# BleSensor.net
KiCad netlist of a schematic drawn in EAGLE
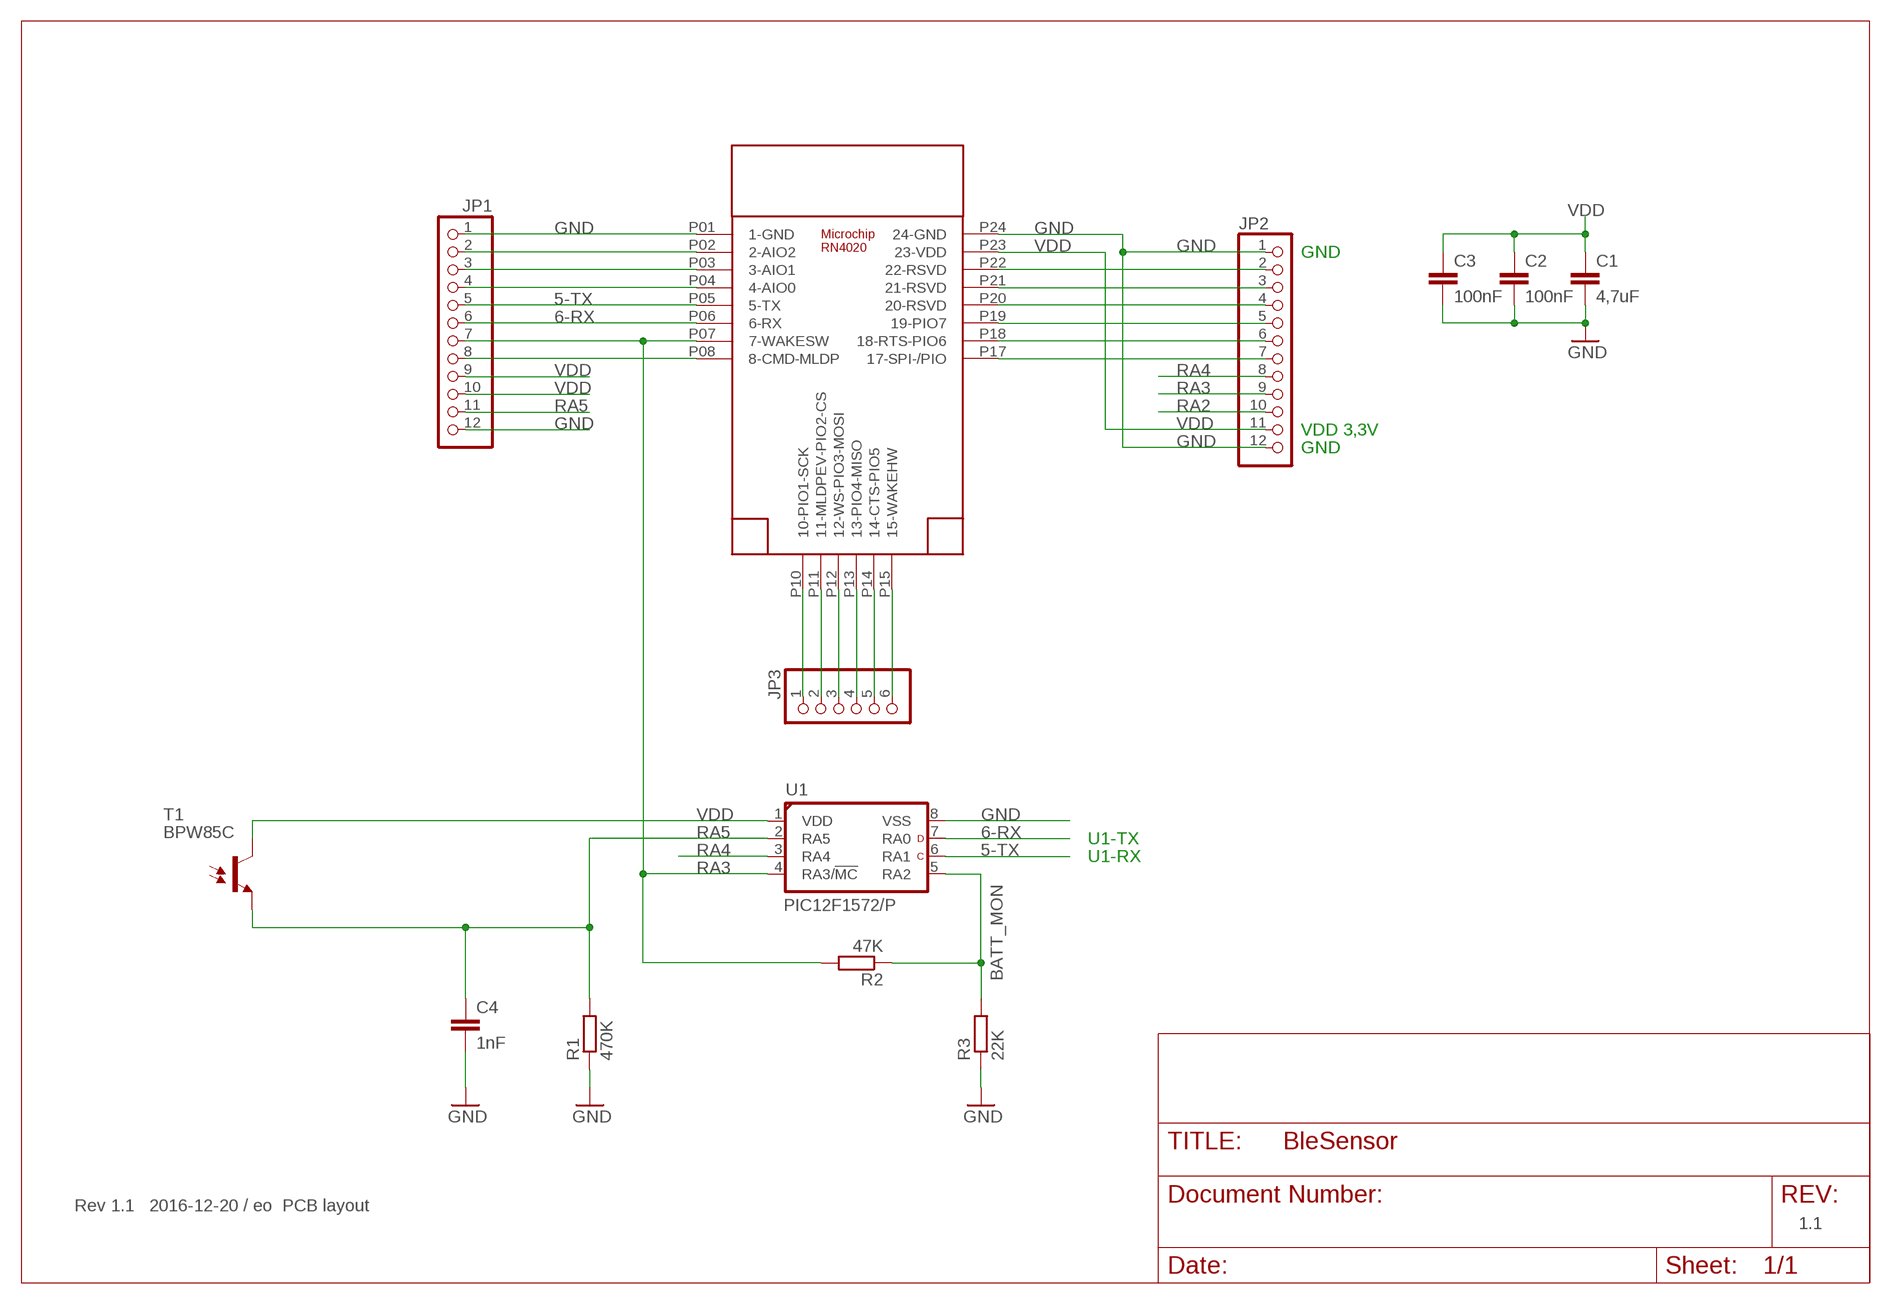
[diagram p0: schematic, sheet 1]

(export (version "E")
  (design (tool "Eeschema 10.0.6"))
  (components
    (comp (ref "C1")
      (value "4,7uF")
      (footprint "eagle-import:C2.5-3")
      (libsource (lib "eagle-import") (part "C2,5-3"))
    )
    (comp (ref "C2")
      (value "100nF")
      (footprint "eagle-import:C1206")
      (libsource (lib "eagle-import") (part "C-EUC1206"))
    )
    (comp (ref "C3")
      (value "100nF")
      (footprint "eagle-import:C1206")
      (libsource (lib "eagle-import") (part "C-EUC1206"))
    )
    (comp (ref "C4")
      (value "1nF")
      (footprint "eagle-import:C1206")
      (libsource (lib "eagle-import") (part "C-EUC1206"))
    )
    (comp (ref "JP1")
      (value "PINHD-1X12")
      (footprint "eagle-import:1X12")
      (libsource (lib "eagle-import") (part "PINHD-1X12"))
    )
    (comp (ref "JP2")
      (value "PINHD-1X12")
      (footprint "eagle-import:1X12")
      (libsource (lib "eagle-import") (part "PINHD-1X12"))
    )
    (comp (ref "JP3")
      (value "PINHD-1X6")
      (footprint "eagle-import:1X06")
      (libsource (lib "eagle-import") (part "PINHD-1X6"))
    )
    (comp (ref "R1")
      (value "470K")
      (footprint "eagle-import:M1206")
      (libsource (lib "eagle-import") (part "R-EU_M1206"))
    )
    (comp (ref "R2")
      (value "47K")
      (footprint "eagle-import:M1206")
      (libsource (lib "eagle-import") (part "R-EU_M1206"))
    )
    (comp (ref "R3")
      (value "22K")
      (footprint "eagle-import:M1206")
      (libsource (lib "eagle-import") (part "R-EU_M1206"))
    )
    (comp (ref "T1")
      (value "BPW85C")
      (footprint "eagle-import:LED3MM")
      (libsource (lib "eagle-import") (part "BPW85C"))
    )
    (comp (ref "U$1")
      (value "RN4020")
      (footprint "eagle-import:RN4020SMD")
      (libsource (lib "eagle-import") (part "RN4020"))
    )
    (comp (ref "U1")
      (value "PIC12F1572/P")
      (footprint "eagle-import:DIL8-P")
      (libsource (lib "eagle-import") (part "PIC12F1572/P"))
    )
  )
  (nets
    (net (code "1") (name "/5-TX") (class "Default")
      (node (ref "JP1") (pin "5") (pinfunction "5_5") (pintype "passive"))
      (node (ref "U$1") (pin "P05") (pinfunction "5-TX_P05") (pintype "bidirectional"))
      (node (ref "U1") (pin "6") (pinfunction "RA1_6") (pintype "bidirectional"))
    )
    (net (code "2") (name "/6-RX") (class "Default")
      (node (ref "JP1") (pin "6") (pinfunction "6_6") (pintype "passive"))
      (node (ref "U$1") (pin "P06") (pinfunction "6-RX_P06") (pintype "bidirectional"))
      (node (ref "U1") (pin "7") (pinfunction "RA0_7") (pintype "bidirectional"))
    )
    (net (code "3") (name "/BATT_MON") (class "Default")
      (node (ref "R2") (pin "1") (pinfunction "1_1") (pintype "passive"))
      (node (ref "R3") (pin "2") (pinfunction "2_2") (pintype "passive"))
      (node (ref "U1") (pin "5") (pinfunction "RA2_5") (pintype "bidirectional"))
    )
    (net (code "4") (name "/RA2") (class "Default")
      (node (ref "JP2") (pin "10") (pinfunction "10_10") (pintype "passive"))
    )
    (net (code "5") (name "/RA3") (class "Default")
      (node (ref "JP1") (pin "7") (pinfunction "7_7") (pintype "passive"))
      (node (ref "JP2") (pin "9") (pinfunction "9_9") (pintype "passive"))
      (node (ref "R2") (pin "2") (pinfunction "2_2") (pintype "passive"))
      (node (ref "U$1") (pin "P07") (pinfunction "7-WAKESW_P07") (pintype "bidirectional"))
      (node (ref "U1") (pin "4") (pinfunction "RA3/~{MC}_4") (pintype "bidirectional"))
    )
    (net (code "6") (name "/RA4") (class "Default")
      (node (ref "JP2") (pin "8") (pinfunction "8_8") (pintype "passive"))
      (node (ref "U1") (pin "3") (pinfunction "RA4_3") (pintype "bidirectional"))
    )
    (net (code "7") (name "/RA5") (class "Default")
      (node (ref "C4") (pin "1") (pinfunction "1_1") (pintype "passive"))
      (node (ref "JP1") (pin "11") (pinfunction "11_11") (pintype "passive"))
      (node (ref "R1") (pin "2") (pinfunction "2_2") (pintype "passive"))
      (node (ref "T1") (pin "A") (pinfunction "E_A") (pintype "passive"))
      (node (ref "U1") (pin "2") (pinfunction "RA5_2") (pintype "bidirectional"))
    )
    (net (code "8") (name "/VDD") (class "Default")
      (node (ref "C1") (pin "1") (pinfunction "1_1") (pintype "passive"))
      (node (ref "C2") (pin "1") (pinfunction "1_1") (pintype "passive"))
      (node (ref "C3") (pin "1") (pinfunction "1_1") (pintype "passive"))
      (node (ref "JP1") (pin "10") (pinfunction "10_10") (pintype "passive"))
      (node (ref "JP1") (pin "9") (pinfunction "9_9") (pintype "passive"))
      (node (ref "JP2") (pin "11") (pinfunction "11_11") (pintype "passive"))
      (node (ref "T1") (pin "K") (pinfunction "C_K") (pintype "passive"))
      (node (ref "U$1") (pin "P23") (pinfunction "23-VDD_P23") (pintype "bidirectional"))
      (node (ref "U1") (pin "1") (pinfunction "VDD_1") (pintype "passive"))
    )
    (net (code "9") (name "GND") (class "Default")
      (node (ref "C1") (pin "2") (pinfunction "2_2") (pintype "passive"))
      (node (ref "C2") (pin "2") (pinfunction "2_2") (pintype "passive"))
      (node (ref "C3") (pin "2") (pinfunction "2_2") (pintype "passive"))
      (node (ref "C4") (pin "2") (pinfunction "2_2") (pintype "passive"))
      (node (ref "JP1") (pin "1") (pinfunction "1_1") (pintype "passive"))
      (node (ref "JP1") (pin "12") (pinfunction "12_12") (pintype "passive"))
      (node (ref "JP2") (pin "1") (pinfunction "1_1") (pintype "passive"))
      (node (ref "JP2") (pin "12") (pinfunction "12_12") (pintype "passive"))
      (node (ref "R1") (pin "1") (pinfunction "1_1") (pintype "passive"))
      (node (ref "R3") (pin "1") (pinfunction "1_1") (pintype "passive"))
      (node (ref "U$1") (pin "P01") (pinfunction "1-GND_P01") (pintype "bidirectional"))
      (node (ref "U$1") (pin "P24") (pinfunction "24-GND_P24") (pintype "bidirectional"))
      (node (ref "U1") (pin "8") (pinfunction "VSS_8") (pintype "passive"))
    )
    (net (code "10") (name "Net-(U$1-2-AIO2)") (class "Default")
      (node (ref "JP1") (pin "2") (pinfunction "2_2") (pintype "passive"))
      (node (ref "U$1") (pin "P02") (pinfunction "2-AIO2_P02") (pintype "bidirectional"))
    )
    (net (code "11") (name "Net-(U$1-3-AIO1)") (class "Default")
      (node (ref "JP1") (pin "3") (pinfunction "3_3") (pintype "passive"))
      (node (ref "U$1") (pin "P03") (pinfunction "3-AIO1_P03") (pintype "bidirectional"))
    )
    (net (code "12") (name "Net-(U$1-4-AIO0)") (class "Default")
      (node (ref "JP1") (pin "4") (pinfunction "4_4") (pintype "passive"))
      (node (ref "U$1") (pin "P04") (pinfunction "4-AIO0_P04") (pintype "bidirectional"))
    )
    (net (code "13") (name "Net-(U$1-8-CMD-MLDP)") (class "Default")
      (node (ref "JP1") (pin "8") (pinfunction "8_8") (pintype "passive"))
      (node (ref "U$1") (pin "P08") (pinfunction "8-CMD-MLDP_P08") (pintype "bidirectional"))
    )
    (net (code "14") (name "Net-(U$1-10-PIO1-SCK)") (class "Default")
      (node (ref "JP3") (pin "1") (pinfunction "1_1") (pintype "passive"))
      (node (ref "U$1") (pin "P10") (pinfunction "10-PIO1-SCK_P10") (pintype "bidirectional"))
    )
    (net (code "15") (name "Net-(U$1-11-MLDPEV-PIO2-CS)") (class "Default")
      (node (ref "JP3") (pin "2") (pinfunction "2_2") (pintype "passive"))
      (node (ref "U$1") (pin "P11") (pinfunction "11-MLDPEV-PIO2-CS_P11") (pintype "bidirectional"))
    )
    (net (code "16") (name "Net-(U$1-12-WS-PIO3-MOSI)") (class "Default")
      (node (ref "JP3") (pin "3") (pinfunction "3_3") (pintype "passive"))
      (node (ref "U$1") (pin "P12") (pinfunction "12-WS-PIO3-MOSI_P12") (pintype "bidirectional"))
    )
    (net (code "17") (name "Net-(U$1-13-PIO4-MISO)") (class "Default")
      (node (ref "JP3") (pin "4") (pinfunction "4_4") (pintype "passive"))
      (node (ref "U$1") (pin "P13") (pinfunction "13-PIO4-MISO_P13") (pintype "bidirectional"))
    )
    (net (code "18") (name "Net-(U$1-14-CTS-PIO5)") (class "Default")
      (node (ref "JP3") (pin "5") (pinfunction "5_5") (pintype "passive"))
      (node (ref "U$1") (pin "P14") (pinfunction "14-CTS-PIO5_P14") (pintype "bidirectional"))
    )
    (net (code "19") (name "Net-(U$1-15-WAKEHW)") (class "Default")
      (node (ref "JP3") (pin "6") (pinfunction "6_6") (pintype "passive"))
      (node (ref "U$1") (pin "P15") (pinfunction "15-WAKEHW_P15") (pintype "bidirectional"))
    )
    (net (code "20") (name "Net-(U$1-17-SPI-{slash}PIO)") (class "Default")
      (node (ref "JP2") (pin "7") (pinfunction "7_7") (pintype "passive"))
      (node (ref "U$1") (pin "P17") (pinfunction "17-SPI-/PIO_P17") (pintype "bidirectional"))
    )
    (net (code "21") (name "Net-(U$1-18-RTS-PIO6)") (class "Default")
      (node (ref "JP2") (pin "6") (pinfunction "6_6") (pintype "passive"))
      (node (ref "U$1") (pin "P18") (pinfunction "18-RTS-PIO6_P18") (pintype "bidirectional"))
    )
    (net (code "22") (name "Net-(U$1-19-PIO7)") (class "Default")
      (node (ref "JP2") (pin "5") (pinfunction "5_5") (pintype "passive"))
      (node (ref "U$1") (pin "P19") (pinfunction "19-PIO7_P19") (pintype "bidirectional"))
    )
    (net (code "23") (name "Net-(U$1-20-RSVD)") (class "Default")
      (node (ref "JP2") (pin "4") (pinfunction "4_4") (pintype "passive"))
      (node (ref "U$1") (pin "P20") (pinfunction "20-RSVD_P20") (pintype "bidirectional"))
    )
    (net (code "24") (name "Net-(U$1-21-RSVD)") (class "Default")
      (node (ref "JP2") (pin "3") (pinfunction "3_3") (pintype "passive"))
      (node (ref "U$1") (pin "P21") (pinfunction "21-RSVD_P21") (pintype "bidirectional"))
    )
    (net (code "25") (name "Net-(U$1-22-RSVD)") (class "Default")
      (node (ref "JP2") (pin "2") (pinfunction "2_2") (pintype "passive"))
      (node (ref "U$1") (pin "P22") (pinfunction "22-RSVD_P22") (pintype "bidirectional"))
    )
  )
)
